# STRAIGT_SENSOR_MUX_16.net
KiCad netlist of a schematic drawn in EAGLE
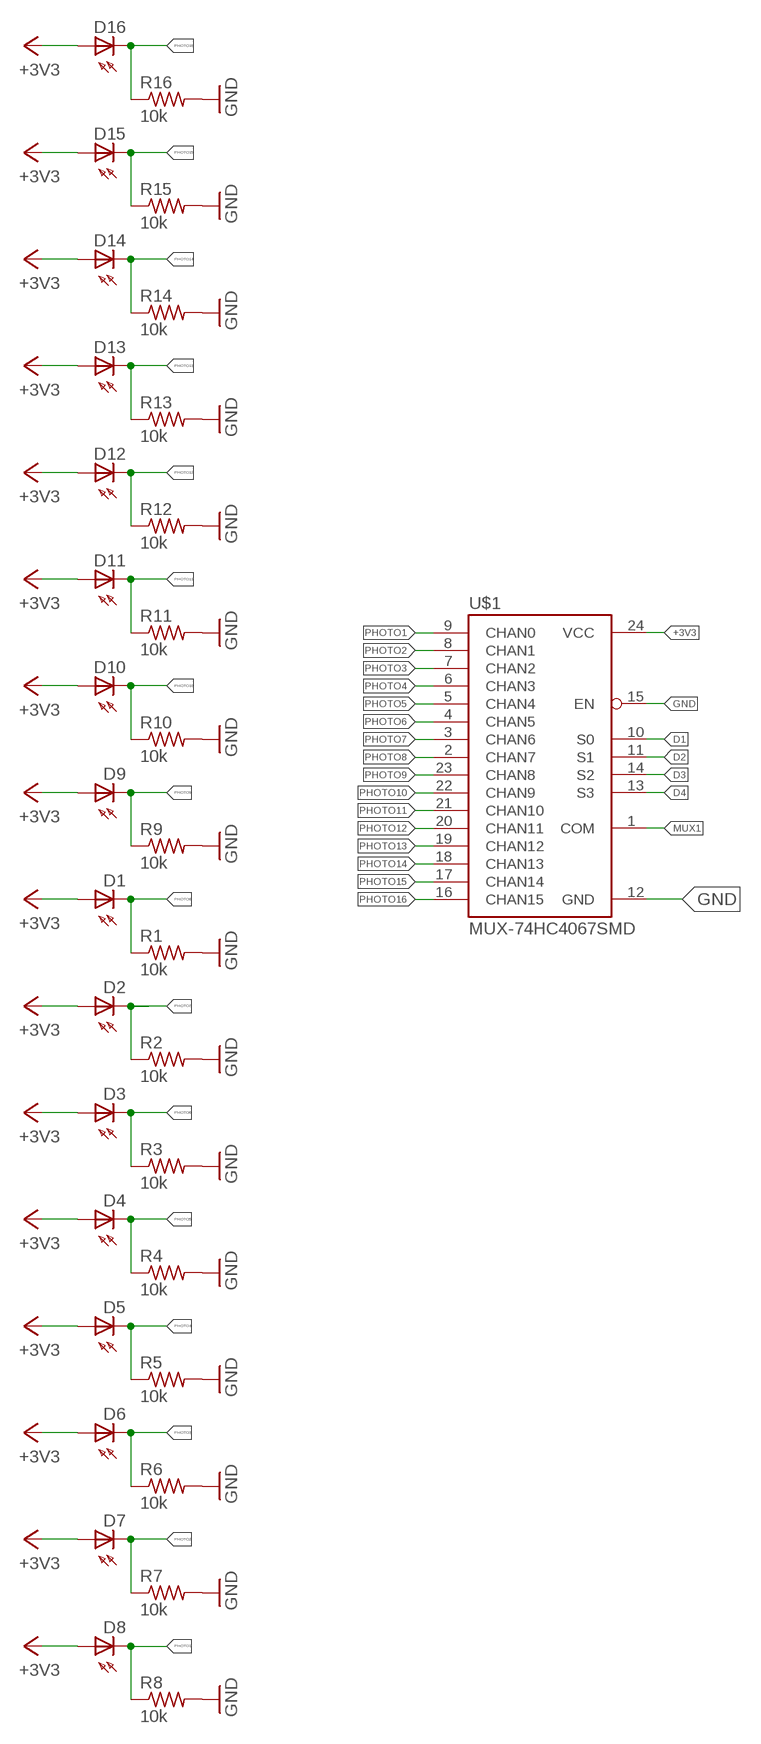
[diagram p0: schematic, sheet 1]

(export (version "E")
  (design (tool "Eeschema 10.0.6"))
  (components
    (comp (ref "D1")
      (value "Photo0")
      (footprint "eagle-import:BPX65")
      (fields (field (name "MPN") "BPX65."))
      (libsource (lib "eagle-import") (part "BPX65"))
    )
    (comp (ref "D2")
      (value "Photo1")
      (footprint "eagle-import:BPX65")
      (fields (field (name "MPN") "BPX65."))
      (libsource (lib "eagle-import") (part "BPX65"))
    )
    (comp (ref "D3")
      (value "Photo2")
      (footprint "eagle-import:BPX65")
      (fields (field (name "MPN") "BPX65."))
      (libsource (lib "eagle-import") (part "BPX65"))
    )
    (comp (ref "D4")
      (value "Photo3")
      (footprint "eagle-import:BPX65")
      (fields (field (name "MPN") "BPX65."))
      (libsource (lib "eagle-import") (part "BPX65"))
    )
    (comp (ref "D5")
      (value "Photo4")
      (footprint "eagle-import:BPX65")
      (fields (field (name "MPN") "BPX65."))
      (libsource (lib "eagle-import") (part "BPX65"))
    )
    (comp (ref "D6")
      (value "Photo5")
      (footprint "eagle-import:BPX65")
      (fields (field (name "MPN") "BPX65."))
      (libsource (lib "eagle-import") (part "BPX65"))
    )
    (comp (ref "D7")
      (value "Photo6")
      (footprint "eagle-import:BPX65")
      (fields (field (name "MPN") "BPX65."))
      (libsource (lib "eagle-import") (part "BPX65"))
    )
    (comp (ref "D8")
      (value "Photo7")
      (footprint "eagle-import:BPX65")
      (fields (field (name "MPN") "BPX65."))
      (libsource (lib "eagle-import") (part "BPX65"))
    )
    (comp (ref "D9")
      (value "Photo0")
      (footprint "eagle-import:BPX65")
      (fields (field (name "MPN") "BPX65."))
      (libsource (lib "eagle-import") (part "BPX65"))
    )
    (comp (ref "D10")
      (value "Photo0")
      (footprint "eagle-import:BPX65")
      (fields (field (name "MPN") "BPX65."))
      (libsource (lib "eagle-import") (part "BPX65"))
    )
    (comp (ref "D11")
      (value "Photo0")
      (footprint "eagle-import:BPX65")
      (fields (field (name "MPN") "BPX65."))
      (libsource (lib "eagle-import") (part "BPX65"))
    )
    (comp (ref "D12")
      (value "Photo0")
      (footprint "eagle-import:BPX65")
      (fields (field (name "MPN") "BPX65."))
      (libsource (lib "eagle-import") (part "BPX65"))
    )
    (comp (ref "D13")
      (value "Photo0")
      (footprint "eagle-import:BPX65")
      (fields (field (name "MPN") "BPX65."))
      (libsource (lib "eagle-import") (part "BPX65"))
    )
    (comp (ref "D14")
      (value "Photo0")
      (footprint "eagle-import:BPX65")
      (fields (field (name "MPN") "BPX65."))
      (libsource (lib "eagle-import") (part "BPX65"))
    )
    (comp (ref "D15")
      (value "Photo0")
      (footprint "eagle-import:BPX65")
      (fields (field (name "MPN") "BPX65."))
      (libsource (lib "eagle-import") (part "BPX65"))
    )
    (comp (ref "D16")
      (value "Photo0")
      (footprint "eagle-import:BPX65")
      (fields (field (name "MPN") "BPX65."))
      (libsource (lib "eagle-import") (part "BPX65"))
    )
    (comp (ref "R1")
      (value "10k")
      (footprint "eagle-import:0207_10")
      (libsource (lib "eagle-import") (part "R-US_0207/10"))
    )
    (comp (ref "R2")
      (value "10k")
      (footprint "eagle-import:0207_10")
      (libsource (lib "eagle-import") (part "R-US_0207/10"))
    )
    (comp (ref "R3")
      (value "10k")
      (footprint "eagle-import:0207_10")
      (libsource (lib "eagle-import") (part "R-US_0207/10"))
    )
    (comp (ref "R4")
      (value "10k")
      (footprint "eagle-import:0207_10")
      (libsource (lib "eagle-import") (part "R-US_0207/10"))
    )
    (comp (ref "R5")
      (value "10k")
      (footprint "eagle-import:0207_10")
      (libsource (lib "eagle-import") (part "R-US_0207/10"))
    )
    (comp (ref "R6")
      (value "10k")
      (footprint "eagle-import:0207_10")
      (libsource (lib "eagle-import") (part "R-US_0207/10"))
    )
    (comp (ref "R7")
      (value "10k")
      (footprint "eagle-import:0207_10")
      (libsource (lib "eagle-import") (part "R-US_0207/10"))
    )
    (comp (ref "R8")
      (value "10k")
      (footprint "eagle-import:0207_10")
      (libsource (lib "eagle-import") (part "R-US_0207/10"))
    )
    (comp (ref "R9")
      (value "10k")
      (footprint "eagle-import:0207_10")
      (libsource (lib "eagle-import") (part "R-US_0207/10"))
    )
    (comp (ref "R10")
      (value "10k")
      (footprint "eagle-import:0207_10")
      (libsource (lib "eagle-import") (part "R-US_0207/10"))
    )
    (comp (ref "R11")
      (value "10k")
      (footprint "eagle-import:0207_10")
      (libsource (lib "eagle-import") (part "R-US_0207/10"))
    )
    (comp (ref "R12")
      (value "10k")
      (footprint "eagle-import:0207_10")
      (libsource (lib "eagle-import") (part "R-US_0207/10"))
    )
    (comp (ref "R13")
      (value "10k")
      (footprint "eagle-import:0207_10")
      (libsource (lib "eagle-import") (part "R-US_0207/10"))
    )
    (comp (ref "R14")
      (value "10k")
      (footprint "eagle-import:0207_10")
      (libsource (lib "eagle-import") (part "R-US_0207/10"))
    )
    (comp (ref "R15")
      (value "10k")
      (footprint "eagle-import:0207_10")
      (libsource (lib "eagle-import") (part "R-US_0207/10"))
    )
    (comp (ref "R16")
      (value "10k")
      (footprint "eagle-import:0207_10")
      (libsource (lib "eagle-import") (part "R-US_0207/10"))
    )
    (comp (ref "U$1")
      (value "MUX-74HC4067SMD")
      (footprint "eagle-import:SSOP24")
      (libsource (lib "eagle-import") (part "MUX-74HC4067SMD"))
    )
  )
  (nets
    (net (code "1") (name "+3V3") (class "Default")
      (node (ref "D1") (pin "A") (pinfunction "A_A") (pintype "passive"))
      (node (ref "D10") (pin "A") (pinfunction "A_A") (pintype "passive"))
      (node (ref "D11") (pin "A") (pinfunction "A_A") (pintype "passive"))
      (node (ref "D12") (pin "A") (pinfunction "A_A") (pintype "passive"))
      (node (ref "D13") (pin "A") (pinfunction "A_A") (pintype "passive"))
      (node (ref "D14") (pin "A") (pinfunction "A_A") (pintype "passive"))
      (node (ref "D15") (pin "A") (pinfunction "A_A") (pintype "passive"))
      (node (ref "D16") (pin "A") (pinfunction "A_A") (pintype "passive"))
      (node (ref "D2") (pin "A") (pinfunction "A_A") (pintype "passive"))
      (node (ref "D3") (pin "A") (pinfunction "A_A") (pintype "passive"))
      (node (ref "D4") (pin "A") (pinfunction "A_A") (pintype "passive"))
      (node (ref "D5") (pin "A") (pinfunction "A_A") (pintype "passive"))
      (node (ref "D6") (pin "A") (pinfunction "A_A") (pintype "passive"))
      (node (ref "D7") (pin "A") (pinfunction "A_A") (pintype "passive"))
      (node (ref "D8") (pin "A") (pinfunction "A_A") (pintype "passive"))
      (node (ref "D9") (pin "A") (pinfunction "A_A") (pintype "passive"))
      (node (ref "U$1") (pin "24") (pinfunction "VCC_24") (pintype "bidirectional"))
    )
    (net (code "2") (name "D1") (class "Default")
      (node (ref "U$1") (pin "10") (pinfunction "S0_10") (pintype "input"))
    )
    (net (code "3") (name "D2") (class "Default")
      (node (ref "U$1") (pin "11") (pinfunction "S1_11") (pintype "input"))
    )
    (net (code "4") (name "D3") (class "Default")
      (node (ref "U$1") (pin "14") (pinfunction "S2_14") (pintype "input"))
    )
    (net (code "5") (name "D4") (class "Default")
      (node (ref "U$1") (pin "13") (pinfunction "S3_13") (pintype "input"))
    )
    (net (code "6") (name "GND") (class "Default")
      (node (ref "R1") (pin "2") (pinfunction "2_2") (pintype "passive"))
      (node (ref "R10") (pin "2") (pinfunction "2_2") (pintype "passive"))
      (node (ref "R11") (pin "2") (pinfunction "2_2") (pintype "passive"))
      (node (ref "R12") (pin "2") (pinfunction "2_2") (pintype "passive"))
      (node (ref "R13") (pin "2") (pinfunction "2_2") (pintype "passive"))
      (node (ref "R14") (pin "2") (pinfunction "2_2") (pintype "passive"))
      (node (ref "R15") (pin "2") (pinfunction "2_2") (pintype "passive"))
      (node (ref "R16") (pin "2") (pinfunction "2_2") (pintype "passive"))
      (node (ref "R2") (pin "2") (pinfunction "2_2") (pintype "passive"))
      (node (ref "R3") (pin "2") (pinfunction "2_2") (pintype "passive"))
      (node (ref "R4") (pin "2") (pinfunction "2_2") (pintype "passive"))
      (node (ref "R5") (pin "2") (pinfunction "2_2") (pintype "passive"))
      (node (ref "R6") (pin "2") (pinfunction "2_2") (pintype "passive"))
      (node (ref "R7") (pin "2") (pinfunction "2_2") (pintype "passive"))
      (node (ref "R8") (pin "2") (pinfunction "2_2") (pintype "passive"))
      (node (ref "R9") (pin "2") (pinfunction "2_2") (pintype "passive"))
      (node (ref "U$1") (pin "12") (pinfunction "GND_12") (pintype "bidirectional"))
      (node (ref "U$1") (pin "15") (pinfunction "EN_15") (pintype "input"))
    )
    (net (code "7") (name "MUX1") (class "Default")
      (node (ref "U$1") (pin "1") (pinfunction "COM_1") (pintype "bidirectional"))
    )
    (net (code "8") (name "PHOTO1") (class "Default")
      (node (ref "D8") (pin "K") (pinfunction "C_K") (pintype "passive"))
      (node (ref "R8") (pin "1") (pinfunction "1_1") (pintype "passive"))
      (node (ref "U$1") (pin "9") (pinfunction "CHAN0_9") (pintype "bidirectional"))
    )
    (net (code "9") (name "PHOTO2") (class "Default")
      (node (ref "D7") (pin "K") (pinfunction "C_K") (pintype "passive"))
      (node (ref "R7") (pin "1") (pinfunction "1_1") (pintype "passive"))
      (node (ref "U$1") (pin "8") (pinfunction "CHAN1_8") (pintype "bidirectional"))
    )
    (net (code "10") (name "PHOTO3") (class "Default")
      (node (ref "D6") (pin "K") (pinfunction "C_K") (pintype "passive"))
      (node (ref "R6") (pin "1") (pinfunction "1_1") (pintype "passive"))
      (node (ref "U$1") (pin "7") (pinfunction "CHAN2_7") (pintype "bidirectional"))
    )
    (net (code "11") (name "PHOTO4") (class "Default")
      (node (ref "D5") (pin "K") (pinfunction "C_K") (pintype "passive"))
      (node (ref "R5") (pin "1") (pinfunction "1_1") (pintype "passive"))
      (node (ref "U$1") (pin "6") (pinfunction "CHAN3_6") (pintype "bidirectional"))
    )
    (net (code "12") (name "PHOTO5") (class "Default")
      (node (ref "D4") (pin "K") (pinfunction "C_K") (pintype "passive"))
      (node (ref "R4") (pin "1") (pinfunction "1_1") (pintype "passive"))
      (node (ref "U$1") (pin "5") (pinfunction "CHAN4_5") (pintype "bidirectional"))
    )
    (net (code "13") (name "PHOTO6") (class "Default")
      (node (ref "D3") (pin "K") (pinfunction "C_K") (pintype "passive"))
      (node (ref "R3") (pin "1") (pinfunction "1_1") (pintype "passive"))
      (node (ref "U$1") (pin "4") (pinfunction "CHAN5_4") (pintype "bidirectional"))
    )
    (net (code "14") (name "PHOTO7") (class "Default")
      (node (ref "D2") (pin "K") (pinfunction "C_K") (pintype "passive"))
      (node (ref "R2") (pin "1") (pinfunction "1_1") (pintype "passive"))
      (node (ref "U$1") (pin "3") (pinfunction "CHAN6_3") (pintype "bidirectional"))
    )
    (net (code "15") (name "PHOTO8") (class "Default")
      (node (ref "D1") (pin "K") (pinfunction "C_K") (pintype "passive"))
      (node (ref "R1") (pin "1") (pinfunction "1_1") (pintype "passive"))
      (node (ref "U$1") (pin "2") (pinfunction "CHAN7_2") (pintype "bidirectional"))
    )
    (net (code "16") (name "PHOTO9") (class "Default")
      (node (ref "D9") (pin "K") (pinfunction "C_K") (pintype "passive"))
      (node (ref "R9") (pin "1") (pinfunction "1_1") (pintype "passive"))
      (node (ref "U$1") (pin "23") (pinfunction "CHAN8_23") (pintype "bidirectional"))
    )
    (net (code "17") (name "PHOTO10") (class "Default")
      (node (ref "D10") (pin "K") (pinfunction "C_K") (pintype "passive"))
      (node (ref "R10") (pin "1") (pinfunction "1_1") (pintype "passive"))
      (node (ref "U$1") (pin "22") (pinfunction "CHAN9_22") (pintype "bidirectional"))
    )
    (net (code "18") (name "PHOTO11") (class "Default")
      (node (ref "D11") (pin "K") (pinfunction "C_K") (pintype "passive"))
      (node (ref "R11") (pin "1") (pinfunction "1_1") (pintype "passive"))
      (node (ref "U$1") (pin "21") (pinfunction "CHAN10_21") (pintype "bidirectional"))
    )
    (net (code "19") (name "PHOTO12") (class "Default")
      (node (ref "D12") (pin "K") (pinfunction "C_K") (pintype "passive"))
      (node (ref "R12") (pin "1") (pinfunction "1_1") (pintype "passive"))
      (node (ref "U$1") (pin "20") (pinfunction "CHAN11_20") (pintype "bidirectional"))
    )
    (net (code "20") (name "PHOTO13") (class "Default")
      (node (ref "D13") (pin "K") (pinfunction "C_K") (pintype "passive"))
      (node (ref "R13") (pin "1") (pinfunction "1_1") (pintype "passive"))
      (node (ref "U$1") (pin "19") (pinfunction "CHAN12_19") (pintype "bidirectional"))
    )
    (net (code "21") (name "PHOTO14") (class "Default")
      (node (ref "D14") (pin "K") (pinfunction "C_K") (pintype "passive"))
      (node (ref "R14") (pin "1") (pinfunction "1_1") (pintype "passive"))
      (node (ref "U$1") (pin "18") (pinfunction "CHAN13_18") (pintype "bidirectional"))
    )
    (net (code "22") (name "PHOTO15") (class "Default")
      (node (ref "D15") (pin "K") (pinfunction "C_K") (pintype "passive"))
      (node (ref "R15") (pin "1") (pinfunction "1_1") (pintype "passive"))
      (node (ref "U$1") (pin "17") (pinfunction "CHAN14_17") (pintype "bidirectional"))
    )
    (net (code "23") (name "PHOTO16") (class "Default")
      (node (ref "D16") (pin "K") (pinfunction "C_K") (pintype "passive"))
      (node (ref "R16") (pin "1") (pinfunction "1_1") (pintype "passive"))
      (node (ref "U$1") (pin "16") (pinfunction "CHAN15_16") (pintype "bidirectional"))
    )
  )
)
